# PMI_Split.net
KiCad netlist of a schematic drawn in Altium Designer
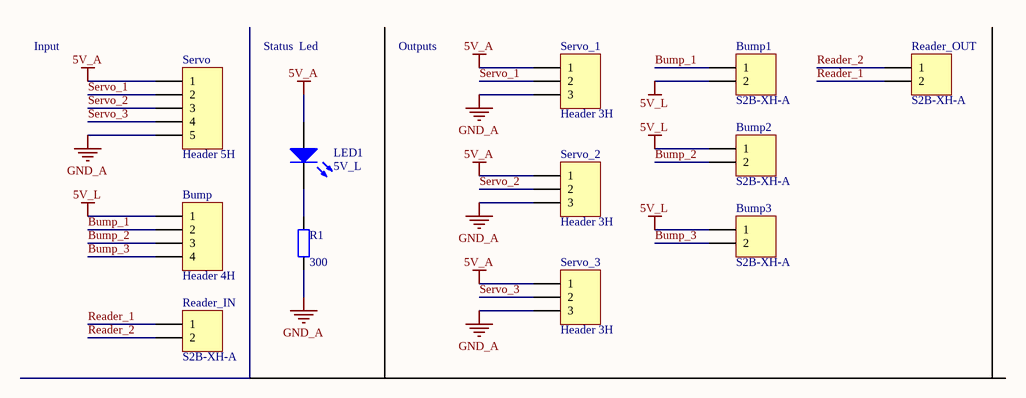
[diagram p0: PMI_Split.SchDoc]

(export (version "E")
  (design (tool "Eeschema 10.0.6"))
  (components
    (comp (ref "Bump")
      (value "Header 4H")
      (footprint "S4B-XH-A")
      (description "Header, 4-Pin, Right Angle")
      (fields (field (name "PUBLISHER") "Altium Limited"))
      (libsource (lib "Miscellaneous Connectors") (part "Header 4H"))
    )
    (comp (ref "Bump1")
      (value "S2B-XH-A")
      (footprint "S2B-XH-A")
      (description "Header, 2-Pin, Right Angle")
      (fields (field (name "PUBLISHER") "Altium Limited"))
      (libsource (lib "Miscellaneous Connectors") (part "Header 2H"))
    )
    (comp (ref "Bump2")
      (value "S2B-XH-A")
      (footprint "S2B-XH-A")
      (description "Header, 2-Pin, Right Angle")
      (fields (field (name "PUBLISHER") "Altium Limited"))
      (libsource (lib "Miscellaneous Connectors") (part "Header 2H"))
    )
    (comp (ref "Bump3")
      (value "S2B-XH-A")
      (footprint "S2B-XH-A")
      (description "Header, 2-Pin, Right Angle")
      (fields (field (name "PUBLISHER") "Altium Limited"))
      (libsource (lib "Miscellaneous Connectors") (part "Header 2H"))
    )
    (comp (ref "LED1")
      (value "5V_L")
      (footprint "KP-3216SEC")
      (description "Typical RED, GREEN, YELLOW, AMBER GaAs LED")
      (fields (field (name "PUBLISHER") "Altium Limited"))
      (libsource (lib "Miscellaneous Devices") (part "LED2"))
    )
    (comp (ref "R1")
      (value "300")
      (footprint "Resistor 1206")
      (description "Resistor")
      (fields (field (name "Comment") "Res2") (field (name "PUBLISHER") "Altium Limited"))
      (libsource (lib "Miscellaneous Devices") (part "Res2"))
    )
    (comp (ref "Reader_IN")
      (value "S2B-XH-A")
      (footprint "S2B-XH-A")
      (description "Header, 2-Pin, Right Angle")
      (fields (field (name "PUBLISHER") "Altium Limited"))
      (libsource (lib "Miscellaneous Connectors") (part "Header 2H"))
    )
    (comp (ref "Reader_OUT")
      (value "S2B-XH-A")
      (footprint "S2B-XH-A")
      (description "Header, 2-Pin, Right Angle")
      (fields (field (name "PUBLISHER") "Altium Limited"))
      (libsource (lib "Miscellaneous Connectors") (part "Header 2H"))
    )
    (comp (ref "Servo")
      (value "Header 5H")
      (footprint "S5B-XH-A")
      (description "Header, 5-Pin, Right Angle")
      (fields (field (name "PUBLISHER") "Altium Limited"))
      (libsource (lib "Miscellaneous Connectors") (part "Header 5H"))
    )
    (comp (ref "Servo_1")
      (value "Header 3H")
      (footprint "S3B-XH-A")
      (description "Header, 3-Pin, Right Angle")
      (fields (field (name "PUBLISHER") "Altium Limited"))
      (libsource (lib "Miscellaneous Connectors") (part "Header 3H"))
    )
    (comp (ref "Servo_2")
      (value "Header 3H")
      (footprint "S3B-XH-A")
      (description "Header, 3-Pin, Right Angle")
      (fields (field (name "PUBLISHER") "Altium Limited"))
      (libsource (lib "Miscellaneous Connectors") (part "Header 3H"))
    )
    (comp (ref "Servo_3")
      (value "Header 3H")
      (footprint "S3B-XH-A")
      (description "Header, 3-Pin, Right Angle")
      (fields (field (name "PUBLISHER") "Altium Limited"))
      (libsource (lib "Miscellaneous Connectors") (part "Header 3H"))
    )
  )
  (nets
    (net (code "1") (name "/Bump_1") (class "Default")
      (node (ref "Bump") (pin "2") (pinfunction "2_2") (pintype "passive"))
      (node (ref "Bump1") (pin "1") (pinfunction "1_1") (pintype "passive"))
    )
    (net (code "2") (name "/Bump_2") (class "Default")
      (node (ref "Bump") (pin "3") (pinfunction "3_3") (pintype "passive"))
      (node (ref "Bump2") (pin "2") (pinfunction "2_2") (pintype "passive"))
    )
    (net (code "3") (name "/Bump_3") (class "Default")
      (node (ref "Bump") (pin "4") (pinfunction "4_4") (pintype "passive"))
      (node (ref "Bump3") (pin "2") (pinfunction "2_2") (pintype "passive"))
    )
    (net (code "4") (name "/Reader_1") (class "Default")
      (node (ref "Reader_IN") (pin "1") (pinfunction "1_1") (pintype "passive"))
      (node (ref "Reader_OUT") (pin "2") (pinfunction "2_2") (pintype "passive"))
    )
    (net (code "5") (name "/Reader_2") (class "Default")
      (node (ref "Reader_IN") (pin "2") (pinfunction "2_2") (pintype "passive"))
      (node (ref "Reader_OUT") (pin "1") (pinfunction "1_1") (pintype "passive"))
    )
    (net (code "6") (name "/Servo_1") (class "Default")
      (node (ref "Servo") (pin "2") (pinfunction "2_2") (pintype "passive"))
      (node (ref "Servo_1") (pin "2") (pinfunction "2_2") (pintype "passive"))
    )
    (net (code "7") (name "/Servo_2") (class "Default")
      (node (ref "Servo") (pin "3") (pinfunction "3_3") (pintype "passive"))
      (node (ref "Servo_2") (pin "2") (pinfunction "2_2") (pintype "passive"))
    )
    (net (code "8") (name "/Servo_3") (class "Default")
      (node (ref "Servo") (pin "4") (pinfunction "4_4") (pintype "passive"))
      (node (ref "Servo_3") (pin "2") (pinfunction "2_2") (pintype "passive"))
    )
    (net (code "9") (name "5V_A") (class "Default")
      (node (ref "LED1") (pin "1") (pinfunction "A_1") (pintype "passive"))
      (node (ref "Servo") (pin "1") (pinfunction "1_1") (pintype "passive"))
      (node (ref "Servo_1") (pin "1") (pinfunction "1_1") (pintype "passive"))
      (node (ref "Servo_2") (pin "1") (pinfunction "1_1") (pintype "passive"))
      (node (ref "Servo_3") (pin "1") (pinfunction "1_1") (pintype "passive"))
    )
    (net (code "10") (name "5V_L") (class "Default")
      (node (ref "Bump") (pin "1") (pinfunction "1_1") (pintype "passive"))
      (node (ref "Bump1") (pin "2") (pinfunction "2_2") (pintype "passive"))
      (node (ref "Bump2") (pin "1") (pinfunction "1_1") (pintype "passive"))
      (node (ref "Bump3") (pin "1") (pinfunction "1_1") (pintype "passive"))
    )
    (net (code "11") (name "GND_A") (class "Default")
      (node (ref "R1") (pin "1") (pinfunction "1_1") (pintype "passive"))
      (node (ref "Servo") (pin "5") (pinfunction "5_5") (pintype "passive"))
      (node (ref "Servo_1") (pin "3") (pinfunction "3_3") (pintype "passive"))
      (node (ref "Servo_2") (pin "3") (pinfunction "3_3") (pintype "passive"))
      (node (ref "Servo_3") (pin "3") (pinfunction "3_3") (pintype "passive"))
    )
    (net (code "12") (name "Net-(LED1-K)") (class "Default")
      (node (ref "LED1") (pin "2") (pinfunction "K_2") (pintype "passive"))
      (node (ref "R1") (pin "2") (pinfunction "2_2") (pintype "passive"))
    )
  )
)
